# STeaMi-FP10-Sortie_Audio.net
KiCad netlist of a schematic drawn in Altium Designer
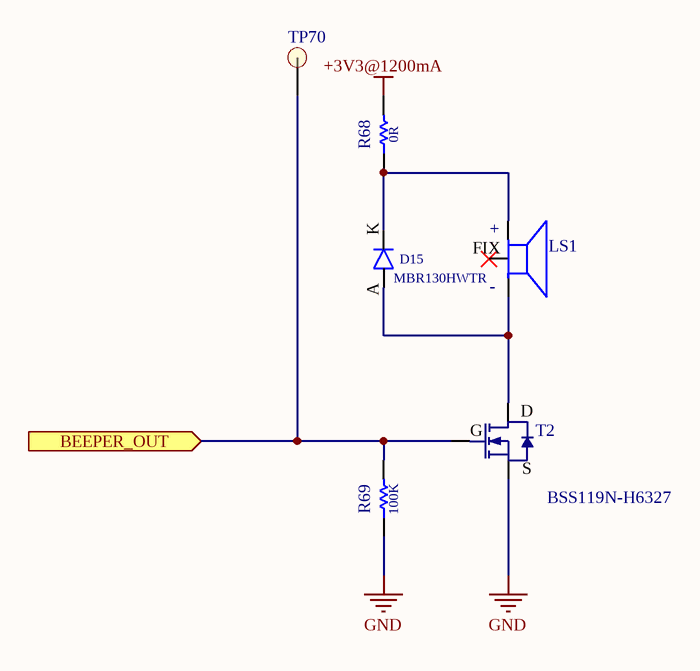
[diagram p0: STeaMi-FP10-Sortie_Audio.SchDoc]

(export (version "E")
  (design (tool "Eeschema 10.0.6"))
  (components
    (comp (ref "D15")
      (value "~")
      (footprint "SOD3615X145N_SOD123")
      (description "Diode Schottky 30 V 1A Montage en surface SOD-123")
      (fields
        (field (name "MANUFACTURER") "SMC diode solutions")
        (field (name "MANUFACTURER PART NUMBER") "MBR130HWTR")
        (field (name "PART NUMBER") "MBR130HWTR")
        (field (name "CREATED BY") "EAG")
      )
      (libsource (lib "ComponentDB") (part "DIODE_SYMBOL"))
    )
    (comp (ref "LS1")
      (value "~")
      (footprint "XDCR_SMT-0825-S-HT-R")
      (description "Speakers & Transducers SURFACE MOUNT TRANSDUCER 3.6 VP-P")
      (fields
        (field (name "MANUFACTURER") "PUI Audio Inc")
        (field (name "PART NUMBER") "SMT-0825-S-HT-R")
        (field (name "CREATED BY") "EAG")
        (field (name "CHECKED BY") "*")
      )
      (libsource (lib "ComponentDB") (part "SMT-0825-S-HT-R"))
    )
    (comp (ref "R68")
      (value "~")
      (footprint "RESC1005X40N_0402")
      (description "RES CMS 0R5%-0,0625W-0402")
      (fields
        (field (name "MANUFACTURER") "Yageo")
        (field (name "MANUFACTURER PART NUMBER") "RC0402JR-100RL")
        (field (name "RESISTANCE") "0R")
        (field (name "CREATED BY") "EAG")
      )
      (libsource (lib "ComponentDB") (part "RES_SYMBOL"))
    )
    (comp (ref "R69")
      (value "~")
      (footprint "RESC1005X40N_0402")
      (description "RES CMS 100K5%-0,0625W-0402 ±100ppm/°C")
      (fields
        (field (name "MANUFACTURER") "Yageo")
        (field (name "MANUFACTURER PART NUMBER") "RC0402JR-07100KL")
        (field (name "RESISTANCE") "100K")
        (field (name "CREATED BY") "EAG")
      )
      (libsource (lib "ComponentDB") (part "RES_SYMBOL"))
    )
    (comp (ref "T2")
      (value "~")
      (footprint "SOT95P260X110-3N_SOT-23-3")
      (description "Small-Signal-Transitor MOSFET N")
      (fields
        (field (name "MANUFACTURER") "Infineon")
        (field (name "MANUFACTURER PART NUMBER") "BSS119N-H6327")
        (field (name "PART NUMBER") "BSS119N")
        (field (name "CHECKED BY") "MSA")
        (field (name "CREATED BY") "EAG")
      )
      (libsource (lib "ComponentDB") (part "BSS119N"))
    )
    (comp (ref "TP70")
      (value "PAD")
      (footprint "Testpoint 1mm")
      (description "TESTPOINTPAD")
      (fields (field (name "MANUFACTURER") "SmartEmbed"))
      (libsource (lib "ComponentDB") (part "TESTPOINT"))
    )
  )
  (nets
    (net (code "1") (name "+3V3@1200mA") (class "Default")
      (node (ref "R68") (pin "2") (pinfunction "2_2") (pintype "passive"))
    )
    (net (code "2") (name "/BEEPER_OUT") (class "Default")
      (node (ref "R69") (pin "2") (pinfunction "2_2") (pintype "passive"))
      (node (ref "T2") (pin "1") (pinfunction "GATE_1") (pintype "passive"))
      (node (ref "TP70") (pin "1") (pinfunction "1_1") (pintype "passive"))
    )
    (net (code "3") (name "GND") (class "Default")
      (node (ref "R69") (pin "1") (pinfunction "1_1") (pintype "passive"))
      (node (ref "T2") (pin "2") (pinfunction "SOURCE_2") (pintype "passive"))
    )
    (net (code "4") (name "Net-(LS1-NEG)") (class "Default")
      (node (ref "D15") (pin "A") (pinfunction "A_A") (pintype "passive"))
      (node (ref "LS1") (pin "N") (pinfunction "NEG_N") (pintype "passive"))
      (node (ref "T2") (pin "3") (pinfunction "DRAIN_3") (pintype "passive"))
    )
    (net (code "5") (name "Net-(LS1-POS)") (class "Default")
      (node (ref "D15") (pin "K") (pinfunction "K_K") (pintype "passive"))
      (node (ref "LS1") (pin "P") (pinfunction "POS_P") (pintype "passive"))
      (node (ref "R68") (pin "1") (pinfunction "1_1") (pintype "passive"))
    )
    (net (code "6") (name "unconnected-(LS1-PadFIX)") (class "Default")
      (node (ref "LS1") (pin "FIX") (pinfunction "FIX_FIX") (pintype "passive+no_connect"))
    )
  )
)
